# ESP32-TEC.net
KiCad netlist of a schematic drawn in Altium Designer
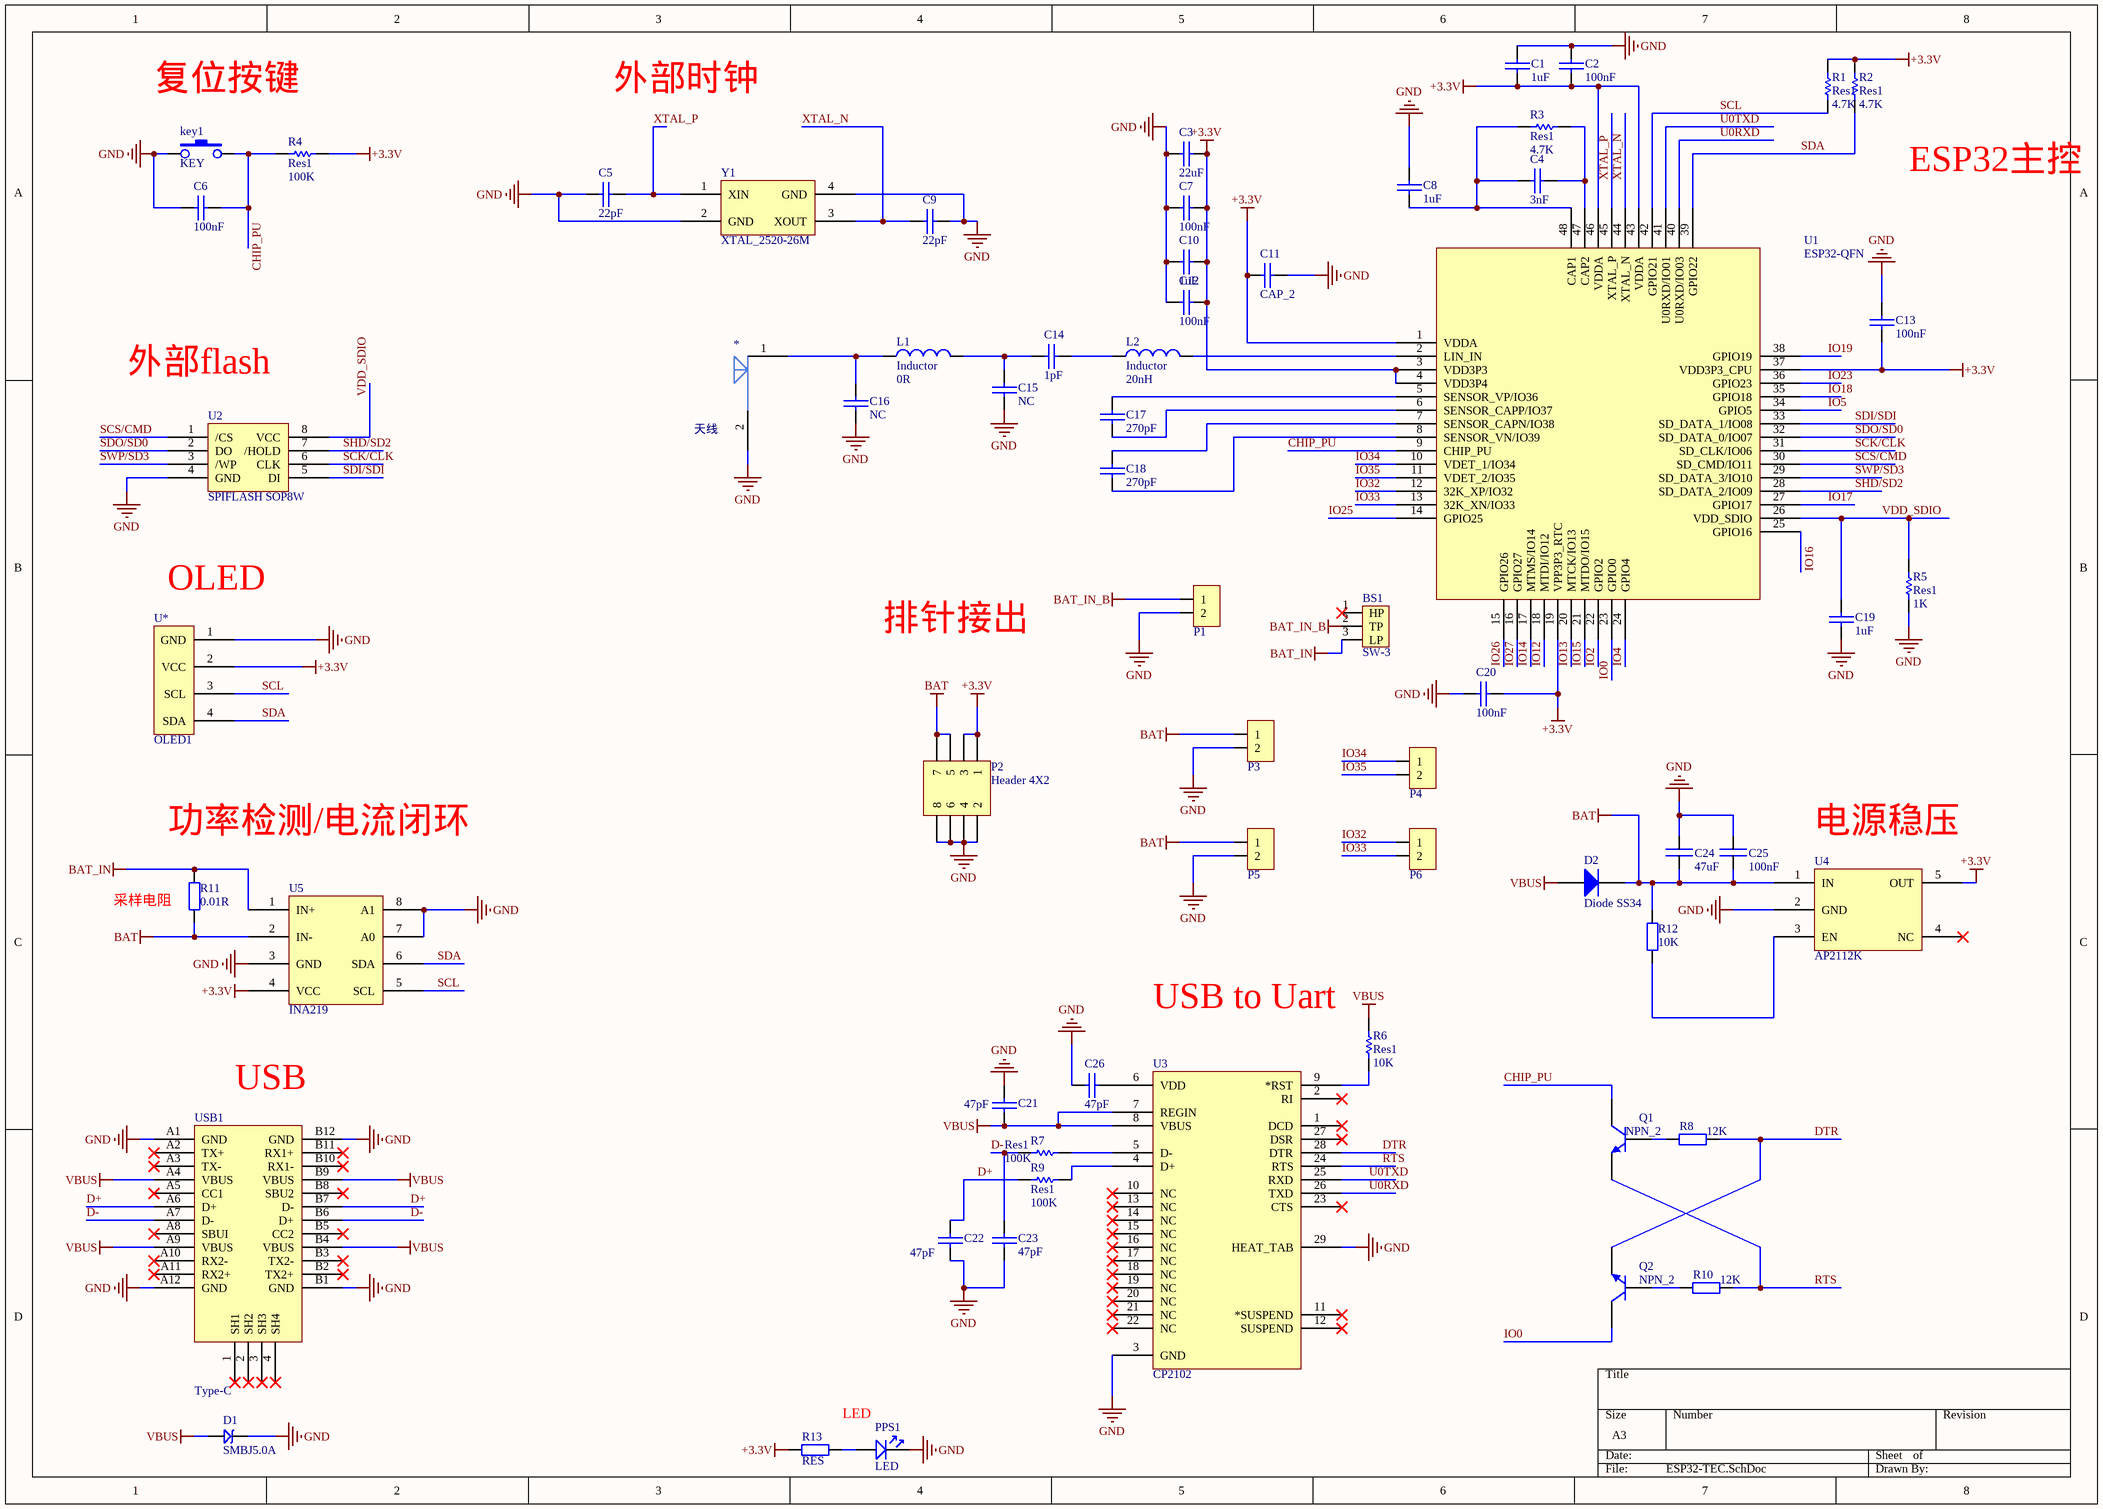
[diagram p0: ESP32-TEC.SchDoc]

(export (version "E")
  (design (tool "Eeschema 10.0.6"))
  (components
    (comp (ref "*") (value "天线") (footprint "WIFI-ANT") (libsource (lib "lyh") (part "天线")))
    (comp (ref "BS1") (value "SW-3") (footprint "纽子开关") (libsource (lib "XH-Library") (part "SW")))
    (comp (ref "C1") (value "1uF") (footprint "0603-C") (libsource (lib "MYSchlib1") (part "CAP_2")))
    (comp (ref "C2") (value "100nF") (footprint "0603-C") (libsource (lib "MYSchlib1") (part "CAP_2")))
    (comp (ref "C3") (value "22uF") (footprint "0603-C") (libsource (lib "MYSchlib1") (part "CAP_2")))
    (comp (ref "C4") (value "3nF") (footprint "0603-C") (libsource (lib "MYSchlib1") (part "CAP_2")))
    (comp (ref "C5") (value "22pF") (footprint "0603-C") (libsource (lib "MYSchlib1") (part "CAP_2")))
    (comp (ref "C6") (value "100nF") (footprint "0603-C") (libsource (lib "MYSchlib1") (part "CAP_2")))
    (comp (ref "C7") (value "100nF") (footprint "0603-C") (libsource (lib "MYSchlib1") (part "CAP_2")))
    (comp (ref "C8") (value "1uF") (footprint "0603-C") (libsource (lib "MYSchlib1") (part "CAP_2")))
    (comp (ref "C9") (value "22pF") (footprint "0603-C") (libsource (lib "MYSchlib1") (part "CAP_2")))
    (comp (ref "C10") (value "1uF") (footprint "0603-C") (libsource (lib "MYSchlib1") (part "CAP_2")))
    (comp (ref "C11") (value "CAP_2") (footprint "0603-C") (libsource (lib "MYSchlib1") (part "CAP_2")))
    (comp (ref "C12") (value "100nF") (footprint "0603-C") (libsource (lib "MYSchlib1") (part "CAP_2")))
    (comp (ref "C13") (value "100nF") (footprint "0603-C") (libsource (lib "MYSchlib1") (part "CAP_2")))
    (comp (ref "C14") (value "1pF") (footprint "0603-C") (libsource (lib "MYSchlib1") (part "CAP_2")))
    (comp (ref "C15") (value "NC") (footprint "0603-C") (libsource (lib "MYSchlib1") (part "CAP_2")))
    (comp (ref "C16") (value "NC") (footprint "0603-C") (libsource (lib "MYSchlib1") (part "CAP_2")))
    (comp (ref "C17") (value "270pF") (footprint "0603-C") (libsource (lib "MYSchlib1") (part "CAP_2")))
    (comp (ref "C18") (value "270pF") (footprint "0603-C") (libsource (lib "MYSchlib1") (part "CAP_2")))
    (comp (ref "C19") (value "1uF") (footprint "0603-C") (libsource (lib "MYSchlib1") (part "CAP_2")))
    (comp (ref "C20") (value "100nF") (footprint "0603-C") (libsource (lib "MYSchlib1") (part "CAP_2")))
    (comp (ref "C21") (value "47pF") (footprint "0603-C") (libsource (lib "MYSchlib1") (part "CAP_2")))
    (comp (ref "C22") (value "47pF") (footprint "0603-C") (libsource (lib "MYSchlib1") (part "CAP_2")))
    (comp (ref "C23") (value "47pF") (footprint "0603-C") (libsource (lib "MYSchlib1") (part "CAP_2")))
    (comp (ref "C24") (value "47uF") (footprint "0603-C") (libsource (lib "MINE") (part "C1_6")))
    (comp (ref "C25") (value "100nF") (footprint "0603-C") (libsource (lib "MINE") (part "C1_6")))
    (comp (ref "C26") (value "47pF") (footprint "0603-C") (libsource (lib "MYSchlib1") (part "CAP_2")))
    (comp (ref "D1")
      (value "SMBJ5.0A")
      (footprint "0603-C")
      (description "TVS")
      (libsource (lib "MINE") (part "SMBJ"))
    )
    (comp (ref "D2")
      (value "Diode SS34")
      (footprint "DIODE-SMA")
      (description "1 Amp General Purpose Rectifier")
      (fields (field (name "PUBLISHER") "Altium Limited"))
      (libsource (lib "MINE") (part "Diode 1N4001"))
    )
    (comp (ref "key1") (value "KEY") (footprint "侧帖按键") (libsource (lib "MYSchlib1") (part "KEY")))
    (comp (ref "L1")
      (value "Inductor")
      (footprint "0603AR")
      (fields (field (name "ALTIUM_VALUE") "0R") (field (name "PUBLISHER") "Altium Limited"))
      (libsource (lib "MYSchlib1") (part "Inductor"))
    )
    (comp (ref "L2")
      (value "Inductor")
      (footprint "0805_L")
      (fields (field (name "ALTIUM_VALUE") "20nH") (field (name "PUBLISHER") "Altium Limited"))
      (libsource (lib "MYSchlib1") (part "Inductor"))
    )
    (comp (ref "P1")
      (value "HDR1X2_180_2.54")
      (footprint "XT-30")
      (description "Header")
      (libsource (lib "MINE") (part "HDR1X2_180_2.54"))
    )
    (comp (ref "P2")
      (value "Header 4X2")
      (footprint "HDR2X4")
      (description "Header, 4-Pin, Dual row")
      (fields (field (name "PUBLISHER") "Altium Limited"))
      (libsource (lib "XH-Library") (part "Header 4X2"))
    )
    (comp (ref "P3")
      (value "HDR1X2_180_2.54")
      (footprint "XT-30")
      (description "Header")
      (libsource (lib "MINE") (part "HDR1X2_180_2.54"))
    )
    (comp (ref "P4")
      (value "HDR1X2_180_2.54")
      (footprint "XT-30")
      (description "Header")
      (libsource (lib "MINE") (part "HDR1X2_180_2.54"))
    )
    (comp (ref "P5")
      (value "HDR1X2_180_2.54")
      (footprint "XT-30")
      (description "Header")
      (libsource (lib "MINE") (part "HDR1X2_180_2.54"))
    )
    (comp (ref "P6")
      (value "HDR1X2_180_2.54")
      (footprint "XT-30")
      (description "Header")
      (libsource (lib "MINE") (part "HDR1X2_180_2.54"))
    )
    (comp (ref "PPS1") (value "LED") (footprint "0603-C") (libsource (lib "XH-Library") (part "LED")))
    (comp (ref "Q1")
      (value "NPN_2")
      (footprint "SOT-23R - duplicate2")
      (description "NPN Bipolar Transistor")
      (fields (field (name "PUBLISHER") "Altium Limited"))
      (libsource (lib "MYSchlib1") (part "NPN_2"))
    )
    (comp (ref "Q2")
      (value "NPN_2")
      (footprint "SOT-23R - duplicate2")
      (description "NPN Bipolar Transistor")
      (fields (field (name "PUBLISHER") "Altium Limited"))
      (libsource (lib "MYSchlib1") (part "NPN_2"))
    )
    (comp (ref "R1")
      (value "Res1")
      (footprint "0603-R")
      (description "Resistor")
      (fields (field (name "ALTIUM_VALUE") "4.7K") (field (name "PUBLISHER") "Altium Limited"))
      (libsource (lib "MYSchlib1") (part "Res1"))
    )
    (comp (ref "R2")
      (value "Res1")
      (footprint "0603-R")
      (description "Resistor")
      (fields (field (name "ALTIUM_VALUE") "4.7K") (field (name "PUBLISHER") "Altium Limited"))
      (libsource (lib "MYSchlib1") (part "Res1"))
    )
    (comp (ref "R3")
      (value "Res1")
      (footprint "0603-R")
      (description "Resistor")
      (fields (field (name "ALTIUM_VALUE") "4.7K") (field (name "PUBLISHER") "Altium Limited"))
      (libsource (lib "MYSchlib1") (part "Res1"))
    )
    (comp (ref "R4")
      (value "Res1")
      (footprint "0603-R")
      (description "Resistor")
      (fields (field (name "ALTIUM_VALUE") "100K") (field (name "PUBLISHER") "Altium Limited"))
      (libsource (lib "MYSchlib1") (part "Res1"))
    )
    (comp (ref "R5")
      (value "Res1")
      (footprint "0603-R")
      (description "Resistor")
      (fields (field (name "ALTIUM_VALUE") "1K") (field (name "PUBLISHER") "Altium Limited"))
      (libsource (lib "MYSchlib1") (part "Res1"))
    )
    (comp (ref "R6")
      (value "Res1")
      (footprint "0603-R")
      (description "Resistor")
      (fields (field (name "ALTIUM_VALUE") "10K") (field (name "PUBLISHER") "Altium Limited"))
      (libsource (lib "MYSchlib1") (part "Res1"))
    )
    (comp (ref "R7")
      (value "Res1")
      (footprint "0603-R")
      (description "Resistor")
      (fields (field (name "ALTIUM_VALUE") "100K") (field (name "PUBLISHER") "Altium Limited"))
      (libsource (lib "MYSchlib1") (part "Res1"))
    )
    (comp (ref "R8")
      (value "12K")
      (footprint "0603-R")
      (description "Resistor")
      (fields (field (name "PUBLISHER") "Altium Limited"))
      (libsource (lib "XH-Library") (part "RES"))
    )
    (comp (ref "R9")
      (value "Res1")
      (footprint "0603-R")
      (description "Resistor")
      (fields (field (name "ALTIUM_VALUE") "100K") (field (name "PUBLISHER") "Altium Limited"))
      (libsource (lib "MYSchlib1") (part "Res1"))
    )
    (comp (ref "R10")
      (value "12K")
      (footprint "0603-R")
      (description "Resistor")
      (fields (field (name "PUBLISHER") "Altium Limited"))
      (libsource (lib "XH-Library") (part "RES"))
    )
    (comp (ref "R11")
      (value "0.01R")
      (footprint "1206")
      (description "Resistor")
      (fields (field (name "PUBLISHER") "Altium Limited"))
      (libsource (lib "") (part "RES_1"))
    )
    (comp (ref "R12")
      (value "10K")
      (footprint "0603-R")
      (description "Resistor")
      (fields (field (name "PUBLISHER") "Altium Limited"))
      (libsource (lib "MINE") (part "RES"))
    )
    (comp (ref "R13")
      (value "RES")
      (footprint "0603P")
      (description "Resistor")
      (fields (field (name "PUBLISHER") "Altium Limited"))
      (libsource (lib "XH-Library") (part "RES"))
    )
    (comp (ref "U*") (value "OLED1") (footprint "HDR1X4") (libsource (lib "lyh") (part "OLED1")))
    (comp (ref "U1") (value "ESP32-QFN") (footprint "QFN48-6x6") (libsource (lib "lyh") (part "ESP32-QFN")))
    (comp (ref "U2")
      (value "SPIFLASH SOP8W")
      (footprint "SOP-8")
      (libsource (lib "lyh") (part "SPIFLASH SOP8W"))
    )
    (comp (ref "U3") (value "CP2102") (footprint "QFN28") (libsource (lib "lyh") (part "CP2102")))
    (comp (ref "U4") (value "AP2112K") (footprint "LC-SOT-23-5") (libsource (lib "lyh") (part "AP2112K")))
    (comp (ref "U5")
      (value "INA219")
      (footprint "LC-SOT-23-8")
      (description "SOT-8")
      (libsource (lib "lyh") (part "INA219"))
    )
    (comp (ref "USB1") (value "Type-C") (footprint "Type-c") (libsource (lib "lyh") (part "Type-C")))
    (comp (ref "Y1")
      (value "XTAL_2520-26M")
      (footprint "2520无源")
      (libsource (lib "lyh") (part "XTAL_2520-26M"))
    )
  )
  (nets
    (net (code "1") (name "+3.3V") (class "Default")
      (node (ref "C1") (pin "2") (pinfunction "2_2") (pintype "passive"))
      (node (ref "C10") (pin "2") (pinfunction "2_2") (pintype "passive"))
      (node (ref "C11") (pin "1") (pinfunction "1_1") (pintype "passive"))
      (node (ref "C12") (pin "2") (pinfunction "2_2") (pintype "passive"))
      (node (ref "C13") (pin "2") (pinfunction "2_2") (pintype "passive"))
      (node (ref "C2") (pin "2") (pinfunction "2_2") (pintype "passive"))
      (node (ref "C20") (pin "1") (pinfunction "1_1") (pintype "passive"))
      (node (ref "C3") (pin "2") (pinfunction "2_2") (pintype "passive"))
      (node (ref "C7") (pin "2") (pinfunction "2_2") (pintype "passive"))
      (node (ref "P2") (pin "1") (pinfunction "1_1") (pintype "passive"))
      (node (ref "P2") (pin "3") (pinfunction "3_3") (pintype "passive"))
      (node (ref "R1") (pin "2") (pinfunction "2_2") (pintype "passive"))
      (node (ref "R13") (pin "1") (pinfunction "1_1") (pintype "passive"))
      (node (ref "R2") (pin "2") (pinfunction "2_2") (pintype "passive"))
      (node (ref "R4") (pin "2") (pinfunction "2_2") (pintype "passive"))
      (node (ref "U*") (pin "2") (pinfunction "VCC_2") (pintype "passive"))
      (node (ref "U1") (pin "1") (pinfunction "VDDA_1") (pintype "passive"))
      (node (ref "U1") (pin "19") (pinfunction "VPP3P3_RTC_19") (pintype "passive"))
      (node (ref "U1") (pin "3") (pinfunction "VDD3P3_3") (pintype "passive"))
      (node (ref "U1") (pin "37") (pinfunction "VDD3P3_CPU_37") (pintype "passive"))
      (node (ref "U1") (pin "4") (pinfunction "VDD3P4_4") (pintype "passive"))
      (node (ref "U1") (pin "43") (pinfunction "VDDA_43") (pintype "passive"))
      (node (ref "U1") (pin "46") (pinfunction "VDDA_46") (pintype "passive"))
      (node (ref "U4") (pin "5") (pinfunction "OUT_5") (pintype "passive"))
      (node (ref "U5") (pin "4") (pinfunction "VCC_4") (pintype "passive"))
    )
    (net (code "2") (name "/CHIP_PU") (class "Default")
      (node (ref "C6") (pin "1") (pinfunction "1_1") (pintype "passive"))
      (node (ref "Q1") (pin "3") (pinfunction "C_3") (pintype "passive"))
      (node (ref "R4") (pin "1") (pinfunction "1_1") (pintype "passive"))
      (node (ref "U1") (pin "9") (pinfunction "CHIP_PU_9") (pintype "passive"))
      (node (ref "key1") (pin "2") (pinfunction "2_2") (pintype "passive"))
    )
    (net (code "3") (name "/D+") (class "Default")
      (node (ref "C22") (pin "2") (pinfunction "2_2") (pintype "passive"))
      (node (ref "R9") (pin "1") (pinfunction "1_1") (pintype "passive"))
      (node (ref "USB1") (pin "A6") (pinfunction "D+_A6") (pintype "passive"))
      (node (ref "USB1") (pin "B7") (pinfunction "D-_B7") (pintype "passive"))
    )
    (net (code "4") (name "/D-") (class "Default")
      (node (ref "C23") (pin "1") (pinfunction "1_1") (pintype "passive"))
      (node (ref "R7") (pin "1") (pinfunction "1_1") (pintype "passive"))
      (node (ref "USB1") (pin "A7") (pinfunction "D-_A7") (pintype "passive"))
      (node (ref "USB1") (pin "B6") (pinfunction "D+_B6") (pintype "passive"))
    )
    (net (code "5") (name "/DTR") (class "Default")
      (node (ref "Q2") (pin "1") (pinfunction "E_1") (pintype "passive"))
      (node (ref "R8") (pin "2") (pinfunction "2_2") (pintype "passive"))
      (node (ref "U3") (pin "28") (pinfunction "DTR_28") (pintype "passive"))
    )
    (net (code "6") (name "/IO0") (class "Default")
      (node (ref "Q2") (pin "3") (pinfunction "C_3") (pintype "passive"))
      (node (ref "U1") (pin "23") (pinfunction "GPIO0_23") (pintype "passive"))
    )
    (net (code "7") (name "/IO2") (class "Default")
      (node (ref "U1") (pin "22") (pinfunction "GPIO2_22") (pintype "passive"))
    )
    (net (code "8") (name "/IO4") (class "Default")
      (node (ref "U1") (pin "24") (pinfunction "GPIO4_24") (pintype "passive"))
    )
    (net (code "9") (name "/IO5") (class "Default")
      (node (ref "U1") (pin "34") (pinfunction "GPIO5_34") (pintype "passive"))
    )
    (net (code "10") (name "/IO12") (class "Default")
      (node (ref "U1") (pin "18") (pinfunction "MTDI/IO12_18") (pintype "passive"))
    )
    (net (code "11") (name "/IO13") (class "Default")
      (node (ref "U1") (pin "20") (pinfunction "MTCK/IO13_20") (pintype "passive"))
    )
    (net (code "12") (name "/IO14") (class "Default")
      (node (ref "U1") (pin "17") (pinfunction "MTMS/IO14_17") (pintype "passive"))
    )
    (net (code "13") (name "/IO15") (class "Default")
      (node (ref "U1") (pin "21") (pinfunction "MTDO/IO15_21") (pintype "passive"))
    )
    (net (code "14") (name "/IO16") (class "Default")
      (node (ref "U1") (pin "25") (pinfunction "GPIO16_25") (pintype "passive"))
    )
    (net (code "15") (name "/IO17") (class "Default")
      (node (ref "U1") (pin "27") (pinfunction "GPIO17_27") (pintype "passive"))
    )
    (net (code "16") (name "/IO18") (class "Default")
      (node (ref "U1") (pin "35") (pinfunction "GPIO18_35") (pintype "passive"))
    )
    (net (code "17") (name "/IO19") (class "Default")
      (node (ref "U1") (pin "38") (pinfunction "GPIO19_38") (pintype "passive"))
    )
    (net (code "18") (name "/IO23") (class "Default")
      (node (ref "U1") (pin "36") (pinfunction "GPIO23_36") (pintype "passive"))
    )
    (net (code "19") (name "/IO25") (class "Default")
      (node (ref "U1") (pin "14") (pinfunction "GPIO25_14") (pintype "passive"))
    )
    (net (code "20") (name "/IO26") (class "Default")
      (node (ref "U1") (pin "15") (pinfunction "GPIO26_15") (pintype "passive"))
    )
    (net (code "21") (name "/IO27") (class "Default")
      (node (ref "U1") (pin "16") (pinfunction "GPIO27_16") (pintype "passive"))
    )
    (net (code "22") (name "/IO32") (class "Default")
      (node (ref "P6") (pin "1") (pinfunction "1_1") (pintype "passive"))
      (node (ref "U1") (pin "12") (pinfunction "32K_XP/IO32_12") (pintype "passive"))
    )
    (net (code "23") (name "/IO33") (class "Default")
      (node (ref "P6") (pin "2") (pinfunction "2_2") (pintype "passive"))
      (node (ref "U1") (pin "13") (pinfunction "32K_XN/IO33_13") (pintype "passive"))
    )
    (net (code "24") (name "/IO34") (class "Default")
      (node (ref "P4") (pin "1") (pinfunction "1_1") (pintype "passive"))
      (node (ref "U1") (pin "10") (pinfunction "VDET_1/IO34_10") (pintype "passive"))
    )
    (net (code "25") (name "/IO35") (class "Default")
      (node (ref "P4") (pin "2") (pinfunction "2_2") (pintype "passive"))
      (node (ref "U1") (pin "11") (pinfunction "VDET_2/IO35_11") (pintype "passive"))
    )
    (net (code "26") (name "/RTS") (class "Default")
      (node (ref "Q1") (pin "1") (pinfunction "E_1") (pintype "passive"))
      (node (ref "R10") (pin "2") (pinfunction "2_2") (pintype "passive"))
      (node (ref "U3") (pin "24") (pinfunction "RTS_24") (pintype "passive"))
    )
    (net (code "27") (name "/SCK{slash}CLK") (class "Default")
      (node (ref "U1") (pin "31") (pinfunction "SD_CLK/IO06_31") (pintype "passive"))
      (node (ref "U2") (pin "6") (pinfunction "CLK_6") (pintype "passive"))
    )
    (net (code "28") (name "/SCL") (class "Default")
      (node (ref "R1") (pin "1") (pinfunction "1_1") (pintype "passive"))
      (node (ref "U*") (pin "3") (pinfunction "SCL_3") (pintype "passive"))
      (node (ref "U1") (pin "42") (pinfunction "GPIO21_42") (pintype "passive"))
      (node (ref "U5") (pin "5") (pinfunction "SCL_5") (pintype "passive"))
    )
    (net (code "29") (name "/SCS{slash}CMD") (class "Default")
      (node (ref "U1") (pin "30") (pinfunction "SD_CMD/IO11_30") (pintype "passive"))
      (node (ref "U2") (pin "1") (pinfunction "/CS_1") (pintype "passive"))
    )
    (net (code "30") (name "/SDA") (class "Default")
      (node (ref "R2") (pin "1") (pinfunction "1_1") (pintype "passive"))
      (node (ref "U*") (pin "4") (pinfunction "SDA_4") (pintype "passive"))
      (node (ref "U1") (pin "39") (pinfunction "GPIO22_39") (pintype "passive"))
      (node (ref "U5") (pin "6") (pinfunction "SDA_6") (pintype "passive"))
    )
    (net (code "31") (name "/SDI{slash}SDI") (class "Default")
      (node (ref "U1") (pin "33") (pinfunction "SD_DATA_1/IO08_33") (pintype "passive"))
      (node (ref "U2") (pin "5") (pinfunction "DI_5") (pintype "passive"))
    )
    (net (code "32") (name "/SDO{slash}SD0") (class "Default")
      (node (ref "U1") (pin "32") (pinfunction "SD_DATA_0/IO07_32") (pintype "passive"))
      (node (ref "U2") (pin "2") (pinfunction "DO_2") (pintype "passive"))
    )
    (net (code "33") (name "/SHD{slash}SD2") (class "Default")
      (node (ref "U1") (pin "28") (pinfunction "SD_DATA_2/IO09_28") (pintype "passive"))
      (node (ref "U2") (pin "7") (pinfunction "/HOLD_7") (pintype "passive"))
    )
    (net (code "34") (name "/SWP{slash}SD3") (class "Default")
      (node (ref "U1") (pin "29") (pinfunction "SD_DATA_3/IO10_29") (pintype "passive"))
      (node (ref "U2") (pin "3") (pinfunction "/WP_3") (pintype "passive"))
    )
    (net (code "35") (name "/U0RXD") (class "Default")
      (node (ref "U1") (pin "40") (pinfunction "U0RXD/IO03_40") (pintype "passive"))
      (node (ref "U3") (pin "26") (pinfunction "TXD_26") (pintype "passive"))
    )
    (net (code "36") (name "/U0TXD") (class "Default")
      (node (ref "U1") (pin "41") (pinfunction "U0RXD/IO01_41") (pintype "passive"))
      (node (ref "U3") (pin "25") (pinfunction "RXD_25") (pintype "passive"))
    )
    (net (code "37") (name "/VDD_SDIO") (class "Default")
      (node (ref "C19") (pin "1") (pinfunction "1_1") (pintype "passive"))
      (node (ref "R5") (pin "2") (pinfunction "2_2") (pintype "passive"))
      (node (ref "U1") (pin "26") (pinfunction "VDD_SDIO_26") (pintype "passive"))
      (node (ref "U2") (pin "8") (pinfunction "VCC_8") (pintype "passive"))
    )
    (net (code "38") (name "/XTAL_N") (class "Default")
      (node (ref "C9") (pin "2") (pinfunction "2_2") (pintype "passive"))
      (node (ref "U1") (pin "44") (pinfunction "XTAL_N_44") (pintype "passive"))
      (node (ref "Y1") (pin "3") (pinfunction "XOUT_3") (pintype "passive"))
    )
    (net (code "39") (name "/XTAL_P") (class "Default")
      (node (ref "C5") (pin "1") (pinfunction "1_1") (pintype "passive"))
      (node (ref "U1") (pin "45") (pinfunction "XTAL_P_45") (pintype "passive"))
      (node (ref "Y1") (pin "1") (pinfunction "XIN_1") (pintype "passive"))
    )
    (net (code "40") (name "BAT") (class "Default")
      (node (ref "C24") (pin "2") (pinfunction "2_2") (pintype "passive"))
      (node (ref "C25") (pin "2") (pinfunction "2_2") (pintype "passive"))
      (node (ref "D2") (pin "2") (pinfunction "K_2") (pintype "passive"))
      (node (ref "P2") (pin "5") (pinfunction "5_5") (pintype "passive"))
      (node (ref "P2") (pin "7") (pinfunction "7_7") (pintype "passive"))
      (node (ref "P3") (pin "1") (pinfunction "1_1") (pintype "passive"))
      (node (ref "P5") (pin "1") (pinfunction "1_1") (pintype "passive"))
      (node (ref "R11") (pin "1") (pinfunction "1_1") (pintype "passive"))
      (node (ref "R12") (pin "2") (pinfunction "2_2") (pintype "passive"))
      (node (ref "U4") (pin "1") (pinfunction "IN_1") (pintype "passive"))
      (node (ref "U5") (pin "2") (pinfunction "IN-_2") (pintype "passive"))
    )
    (net (code "41") (name "BAT_IN") (class "Default")
      (node (ref "BS1") (pin "3") (pinfunction "LP_3") (pintype "passive"))
      (node (ref "R11") (pin "2") (pinfunction "2_2") (pintype "passive"))
      (node (ref "U5") (pin "1") (pinfunction "IN+_1") (pintype "passive"))
    )
    (net (code "42") (name "BAT_IN_B") (class "Default")
      (node (ref "BS1") (pin "2") (pinfunction "TP_2") (pintype "passive"))
      (node (ref "P1") (pin "1") (pinfunction "1_1") (pintype "passive"))
    )
    (net (code "43") (name "GND") (class "Default")
      (node (ref "*") (pin "2") (pintype "passive"))
      (node (ref "C1") (pin "1") (pinfunction "1_1") (pintype "passive"))
      (node (ref "C10") (pin "1") (pinfunction "1_1") (pintype "passive"))
      (node (ref "C11") (pin "2") (pinfunction "2_2") (pintype "passive"))
      (node (ref "C12") (pin "1") (pinfunction "1_1") (pintype "passive"))
      (node (ref "C13") (pin "1") (pinfunction "1_1") (pintype "passive"))
      (node (ref "C15") (pin "1") (pinfunction "1_1") (pintype "passive"))
      (node (ref "C16") (pin "1") (pinfunction "1_1") (pintype "passive"))
      (node (ref "C19") (pin "2") (pinfunction "2_2") (pintype "passive"))
      (node (ref "C2") (pin "1") (pinfunction "1_1") (pintype "passive"))
      (node (ref "C20") (pin "2") (pinfunction "2_2") (pintype "passive"))
      (node (ref "C21") (pin "2") (pinfunction "2_2") (pintype "passive"))
      (node (ref "C22") (pin "1") (pinfunction "1_1") (pintype "passive"))
      (node (ref "C23") (pin "2") (pinfunction "2_2") (pintype "passive"))
      (node (ref "C24") (pin "1") (pinfunction "1_1") (pintype "passive"))
      (node (ref "C25") (pin "1") (pinfunction "1_1") (pintype "passive"))
      (node (ref "C26") (pin "2") (pinfunction "2_2") (pintype "passive"))
      (node (ref "C3") (pin "1") (pinfunction "1_1") (pintype "passive"))
      (node (ref "C5") (pin "2") (pinfunction "2_2") (pintype "passive"))
      (node (ref "C6") (pin "2") (pinfunction "2_2") (pintype "passive"))
      (node (ref "C7") (pin "1") (pinfunction "1_1") (pintype "passive"))
      (node (ref "C8") (pin "1") (pinfunction "1_1") (pintype "passive"))
      (node (ref "C9") (pin "1") (pinfunction "1_1") (pintype "passive"))
      (node (ref "D1") (pin "2") (pintype "passive"))
      (node (ref "P1") (pin "2") (pinfunction "2_2") (pintype "passive"))
      (node (ref "P2") (pin "2") (pinfunction "2_2") (pintype "passive"))
      (node (ref "P2") (pin "4") (pinfunction "4_4") (pintype "passive"))
      (node (ref "P2") (pin "6") (pinfunction "6_6") (pintype "passive"))
      (node (ref "P2") (pin "8") (pinfunction "8_8") (pintype "passive"))
      (node (ref "P3") (pin "2") (pinfunction "2_2") (pintype "passive"))
      (node (ref "P5") (pin "2") (pinfunction "2_2") (pintype "passive"))
      (node (ref "PPS1") (pin "2") (pinfunction "2_2") (pintype "passive"))
      (node (ref "R5") (pin "1") (pinfunction "1_1") (pintype "passive"))
      (node (ref "U*") (pin "1") (pinfunction "GND_1") (pintype "passive"))
      (node (ref "U2") (pin "4") (pinfunction "GND_4") (pintype "passive"))
      (node (ref "U3") (pin "29") (pinfunction "HEAT_TAB_29") (pintype "passive"))
      (node (ref "U3") (pin "3") (pinfunction "GND_3") (pintype "passive"))
      (node (ref "U4") (pin "2") (pinfunction "GND_2") (pintype "passive"))
      (node (ref "U5") (pin "3") (pinfunction "GND_3") (pintype "passive"))
      (node (ref "U5") (pin "7") (pinfunction "A0_7") (pintype "passive"))
      (node (ref "U5") (pin "8") (pinfunction "A1_8") (pintype "passive"))
      (node (ref "USB1") (pin "A1") (pinfunction "GND_A1") (pintype "passive"))
      (node (ref "USB1") (pin "A12") (pinfunction "GND_A12") (pintype "passive"))
      (node (ref "USB1") (pin "B1") (pinfunction "GND_B1") (pintype "passive"))
      (node (ref "USB1") (pin "B12") (pinfunction "GND_B12") (pintype "passive"))
      (node (ref "Y1") (pin "2") (pinfunction "GND_2") (pintype "passive"))
      (node (ref "Y1") (pin "4") (pinfunction "GND_4") (pintype "passive"))
      (node (ref "key1") (pin "1") (pinfunction "1_1") (pintype "passive"))
    )
    (net (code "44") (name "Net-(*-Pad1)") (class "Default")
      (node (ref "*") (pin "1") (pintype "passive"))
      (node (ref "C16") (pin "2") (pinfunction "2_2") (pintype "passive"))
      (node (ref "L1") (pin "1") (pinfunction "1_1") (pintype "passive"))
    )
    (net (code "45") (name "Net-(C14-Pad1)") (class "Default")
      (node (ref "C14") (pin "1") (pinfunction "1_1") (pintype "passive"))
      (node (ref "C15") (pin "2") (pinfunction "2_2") (pintype "passive"))
      (node (ref "L1") (pin "2") (pinfunction "2_2") (pintype "passive"))
    )
    (net (code "46") (name "Net-(C14-Pad2)") (class "Default")
      (node (ref "C14") (pin "2") (pinfunction "2_2") (pintype "passive"))
      (node (ref "L2") (pin "1") (pinfunction "1_1") (pintype "passive"))
    )
    (net (code "47") (name "Net-(PPS1-Pad1)") (class "Default")
      (node (ref "PPS1") (pin "1") (pinfunction "1_1") (pintype "passive"))
      (node (ref "R13") (pin "2") (pinfunction "2_2") (pintype "passive"))
    )
    (net (code "48") (name "Net-(Q1-B)") (class "Default")
      (node (ref "Q1") (pin "2") (pinfunction "B_2") (pintype "passive"))
      (node (ref "R8") (pin "1") (pinfunction "1_1") (pintype "passive"))
    )
    (net (code "49") (name "Net-(Q2-B)") (class "Default")
      (node (ref "Q2") (pin "2") (pinfunction "B_2") (pintype "passive"))
      (node (ref "R10") (pin "1") (pinfunction "1_1") (pintype "passive"))
    )
    (net (code "50") (name "Net-(U1-CAP1)") (class "Default")
      (node (ref "C4") (pin "1") (pinfunction "1_1") (pintype "passive"))
      (node (ref "C8") (pin "2") (pinfunction "2_2") (pintype "passive"))
      (node (ref "R3") (pin "2") (pinfunction "2_2") (pintype "passive"))
      (node (ref "U1") (pin "48") (pinfunction "CAP1_48") (pintype "passive"))
    )
    (net (code "51") (name "Net-(U1-CAP2)") (class "Default")
      (node (ref "C4") (pin "2") (pinfunction "2_2") (pintype "passive"))
      (node (ref "R3") (pin "1") (pinfunction "1_1") (pintype "passive"))
      (node (ref "U1") (pin "47") (pinfunction "CAP2_47") (pintype "passive"))
    )
    (net (code "52") (name "Net-(U1-LIN_IN)") (class "Default")
      (node (ref "L2") (pin "2") (pinfunction "2_2") (pintype "passive"))
      (node (ref "U1") (pin "2") (pinfunction "LIN_IN_2") (pintype "passive"))
    )
    (net (code "53") (name "Net-(U1-SENSOR_CAPN{slash}IO38)") (class "Default")
      (node (ref "C18") (pin "2") (pinfunction "2_2") (pintype "passive"))
      (node (ref "U1") (pin "7") (pinfunction "SENSOR_CAPN/IO38_7") (pintype "passive"))
    )
    (net (code "54") (name "Net-(U1-SENSOR_CAPP{slash}IO37)") (class "Default")
      (node (ref "C17") (pin "1") (pinfunction "1_1") (pintype "passive"))
      (node (ref "U1") (pin "6") (pinfunction "SENSOR_CAPP/IO37_6") (pintype "passive"))
    )
    (net (code "55") (name "Net-(U1-SENSOR_VN{slash}IO39)") (class "Default")
      (node (ref "C18") (pin "1") (pinfunction "1_1") (pintype "passive"))
      (node (ref "U1") (pin "8") (pinfunction "SENSOR_VN/IO39_8") (pintype "passive"))
    )
    (net (code "56") (name "Net-(U1-SENSOR_VP{slash}IO36)") (class "Default")
      (node (ref "C17") (pin "2") (pinfunction "2_2") (pintype "passive"))
      (node (ref "U1") (pin "5") (pinfunction "SENSOR_VP/IO36_5") (pintype "passive"))
    )
    (net (code "57") (name "Net-(U3-*RST)") (class "Default")
      (node (ref "R6") (pin "1") (pinfunction "1_1") (pintype "passive"))
      (node (ref "U3") (pin "9") (pinfunction "*RST_9") (pintype "passive"))
    )
    (net (code "58") (name "Net-(U3-D+)") (class "Default")
      (node (ref "R9") (pin "2") (pinfunction "2_2") (pintype "passive"))
      (node (ref "U3") (pin "4") (pinfunction "D+_4") (pintype "passive"))
    )
    (net (code "59") (name "Net-(U3-D-)") (class "Default")
      (node (ref "R7") (pin "2") (pinfunction "2_2") (pintype "passive"))
      (node (ref "U3") (pin "5") (pinfunction "D-_5") (pintype "passive"))
    )
    (net (code "60") (name "Net-(U3-VDD)") (class "Default")
      (node (ref "C26") (pin "1") (pinfunction "1_1") (pintype "passive"))
      (node (ref "U3") (pin "6") (pinfunction "VDD_6") (pintype "passive"))
    )
    (net (code "61") (name "Net-(U4-EN)") (class "Default")
      (node (ref "R12") (pin "1") (pinfunction "1_1") (pintype "passive"))
      (node (ref "U4") (pin "3") (pinfunction "EN_3") (pintype "passive"))
    )
    (net (code "62") (name "VBUS") (class "Default")
      (node (ref "C21") (pin "1") (pinfunction "1_1") (pintype "passive"))
      (node (ref "D1") (pin "1") (pintype "passive"))
      (node (ref "D2") (pin "1") (pinfunction "A_1") (pintype "passive"))
      (node (ref "R6") (pin "2") (pinfunction "2_2") (pintype "passive"))
      (node (ref "U3") (pin "7") (pinfunction "REGIN_7") (pintype "passive"))
      (node (ref "U3") (pin "8") (pinfunction "VBUS_8") (pintype "passive"))
      (node (ref "USB1") (pin "A4") (pinfunction "VBUS_A4") (pintype "passive"))
      (node (ref "USB1") (pin "A9") (pinfunction "VBUS_A9") (pintype "passive"))
      (node (ref "USB1") (pin "B4") (pinfunction "VBUS_B4") (pintype "passive"))
      (node (ref "USB1") (pin "B9") (pinfunction "VBUS_B9") (pintype "passive"))
    )
    (net (code "63") (name "unconnected-(BS1-HP-Pad1)") (class "Default")
      (node (ref "BS1") (pin "1") (pinfunction "HP_1") (pintype "passive+no_connect"))
    )
    (net (code "64") (name "unconnected-(U3-*SUSPEND-Pad11)") (class "Default")
      (node (ref "U3") (pin "11") (pinfunction "*SUSPEND_11") (pintype "passive+no_connect"))
    )
    (net (code "65") (name "unconnected-(U3-CTS-Pad23)") (class "Default")
      (node (ref "U3") (pin "23") (pinfunction "CTS_23") (pintype "passive+no_connect"))
    )
    (net (code "66") (name "unconnected-(U3-DCD-Pad1)") (class "Default")
      (node (ref "U3") (pin "1") (pinfunction "DCD_1") (pintype "passive+no_connect"))
    )
    (net (code "67") (name "unconnected-(U3-DSR-Pad27)") (class "Default")
      (node (ref "U3") (pin "27") (pinfunction "DSR_27") (pintype "passive+no_connect"))
    )
    (net (code "68") (name "unconnected-(U3-NC-Pad10)") (class "Default")
      (node (ref "U3") (pin "10") (pinfunction "NC_10") (pintype "passive+no_connect"))
    )
    (net (code "69") (name "unconnected-(U3-NC-Pad13)") (class "Default")
      (node (ref "U3") (pin "13") (pinfunction "NC_13") (pintype "passive+no_connect"))
    )
    (net (code "70") (name "unconnected-(U3-NC-Pad14)") (class "Default")
      (node (ref "U3") (pin "14") (pinfunction "NC_14") (pintype "passive+no_connect"))
    )
    (net (code "71") (name "unconnected-(U3-NC-Pad15)") (class "Default")
      (node (ref "U3") (pin "15") (pinfunction "NC_15") (pintype "passive+no_connect"))
    )
    (net (code "72") (name "unconnected-(U3-NC-Pad16)") (class "Default")
      (node (ref "U3") (pin "16") (pinfunction "NC_16") (pintype "passive+no_connect"))
    )
    (net (code "73") (name "unconnected-(U3-NC-Pad17)") (class "Default")
      (node (ref "U3") (pin "17") (pinfunction "NC_17") (pintype "passive+no_connect"))
    )
    (net (code "74") (name "unconnected-(U3-NC-Pad18)") (class "Default")
      (node (ref "U3") (pin "18") (pinfunction "NC_18") (pintype "passive+no_connect"))
    )
    (net (code "75") (name "unconnected-(U3-NC-Pad19)") (class "Default")
      (node (ref "U3") (pin "19") (pinfunction "NC_19") (pintype "passive+no_connect"))
    )
    (net (code "76") (name "unconnected-(U3-NC-Pad20)") (class "Default")
      (node (ref "U3") (pin "20") (pinfunction "NC_20") (pintype "passive+no_connect"))
    )
    (net (code "77") (name "unconnected-(U3-NC-Pad21)") (class "Default")
      (node (ref "U3") (pin "21") (pinfunction "NC_21") (pintype "passive+no_connect"))
    )
    (net (code "78") (name "unconnected-(U3-NC-Pad22)") (class "Default")
      (node (ref "U3") (pin "22") (pinfunction "NC_22") (pintype "passive+no_connect"))
    )
    (net (code "79") (name "unconnected-(U3-RI-Pad2)") (class "Default")
      (node (ref "U3") (pin "2") (pinfunction "RI_2") (pintype "passive+no_connect"))
    )
    (net (code "80") (name "unconnected-(U3-SUSPEND-Pad12)") (class "Default")
      (node (ref "U3") (pin "12") (pinfunction "SUSPEND_12") (pintype "passive+no_connect"))
    )
    (net (code "81") (name "unconnected-(U4-NC-Pad4)") (class "Default")
      (node (ref "U4") (pin "4") (pinfunction "NC_4") (pintype "passive+no_connect"))
    )
    (net (code "82") (name "unconnected-(USB1-CC1-PadA5)") (class "Default")
      (node (ref "USB1") (pin "A5") (pinfunction "CC1_A5") (pintype "passive+no_connect"))
    )
    (net (code "83") (name "unconnected-(USB1-CC2-PadB5)") (class "Default")
      (node (ref "USB1") (pin "B5") (pinfunction "CC2_B5") (pintype "passive+no_connect"))
    )
    (net (code "84") (name "unconnected-(USB1-RX1+-PadB11)") (class "Default")
      (node (ref "USB1") (pin "B11") (pinfunction "RX1+_B11") (pintype "passive+no_connect"))
    )
    (net (code "85") (name "unconnected-(USB1-RX1--PadB10)") (class "Default")
      (node (ref "USB1") (pin "B10") (pinfunction "RX1-_B10") (pintype "passive+no_connect"))
    )
    (net (code "86") (name "unconnected-(USB1-RX2+-PadA11)") (class "Default")
      (node (ref "USB1") (pin "A11") (pinfunction "RX2+_A11") (pintype "passive+no_connect"))
    )
    (net (code "87") (name "unconnected-(USB1-RX2--PadA10)") (class "Default")
      (node (ref "USB1") (pin "A10") (pinfunction "RX2-_A10") (pintype "passive+no_connect"))
    )
    (net (code "88") (name "unconnected-(USB1-SBU2-PadB8)") (class "Default")
      (node (ref "USB1") (pin "B8") (pinfunction "SBU2_B8") (pintype "passive+no_connect"))
    )
    (net (code "89") (name "unconnected-(USB1-SBUI-PadA8)") (class "Default")
      (node (ref "USB1") (pin "A8") (pinfunction "SBUI_A8") (pintype "passive+no_connect"))
    )
    (net (code "90") (name "unconnected-(USB1-SH1-Pad1)") (class "Default")
      (node (ref "USB1") (pin "1") (pinfunction "SH1_1") (pintype "passive+no_connect"))
    )
    (net (code "91") (name "unconnected-(USB1-SH2-Pad2)") (class "Default")
      (node (ref "USB1") (pin "2") (pinfunction "SH2_2") (pintype "passive+no_connect"))
    )
    (net (code "92") (name "unconnected-(USB1-SH3-Pad3)") (class "Default")
      (node (ref "USB1") (pin "3") (pinfunction "SH3_3") (pintype "passive+no_connect"))
    )
    (net (code "93") (name "unconnected-(USB1-SH4-Pad4)") (class "Default")
      (node (ref "USB1") (pin "4") (pinfunction "SH4_4") (pintype "passive+no_connect"))
    )
    (net (code "94") (name "unconnected-(USB1-TX+-PadA2)") (class "Default")
      (node (ref "USB1") (pin "A2") (pinfunction "TX+_A2") (pintype "passive+no_connect"))
    )
    (net (code "95") (name "unconnected-(USB1-TX--PadA3)") (class "Default")
      (node (ref "USB1") (pin "A3") (pinfunction "TX-_A3") (pintype "passive+no_connect"))
    )
    (net (code "96") (name "unconnected-(USB1-TX2+-PadB2)") (class "Default")
      (node (ref "USB1") (pin "B2") (pinfunction "TX2+_B2") (pintype "passive+no_connect"))
    )
    (net (code "97") (name "unconnected-(USB1-TX2--PadB3)") (class "Default")
      (node (ref "USB1") (pin "B3") (pinfunction "TX2-_B3") (pintype "passive+no_connect"))
    )
  )
)
